# SOC_EMMC_SDMMC_PCIE_ADC.net
KiCad netlist of a schematic drawn in Altium Designer
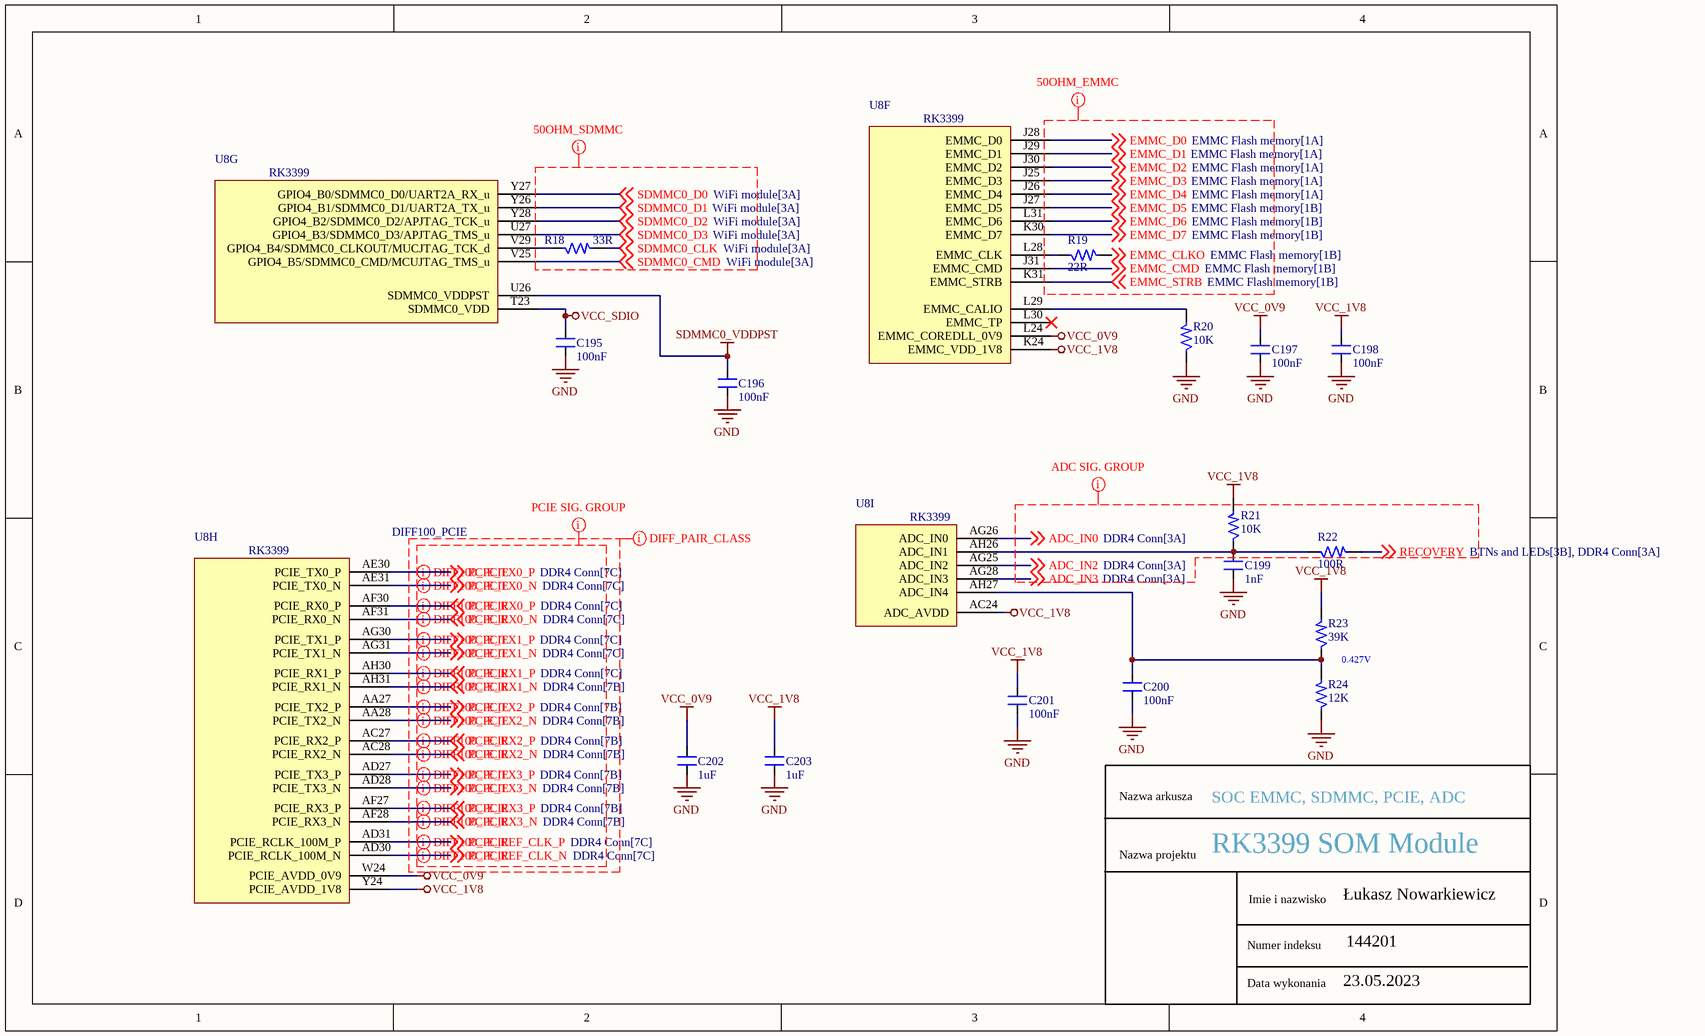
[diagram p0: SOC EMMC, SDMMC, PCIE, ADC.SchDoc]

(export (version "E")
  (design (tool "Eeschema 10.0.6"))
  (components
    (comp (ref "C195")
      (value "100nF")
      (footprint "CAP_0201")
      (description "0.1µF ±10% 25V Ceramic Capacitor X5R 0201 (0603 Metric)")
      (fields
        (field (name "MANUFACTURER") "TDK Corporation")
        (field (name "MANUFACTURER PART NUMBER") "C0603X5R1E104K030BB")
      )
      (libsource (lib "RK3399 _Module_Intlib") (part "CAP_100nF-25V-10%-0201"))
    )
    (comp (ref "C196")
      (value "100nF")
      (footprint "CAP_0201")
      (description "0.1µF ±10% 25V Ceramic Capacitor X5R 0201 (0603 Metric)")
      (fields
        (field (name "MANUFACTURER") "TDK Corporation")
        (field (name "MANUFACTURER PART NUMBER") "C0603X5R1E104K030BB")
      )
      (libsource (lib "RK3399 _Module_Intlib") (part "CAP_100nF-25V-10%-0201"))
    )
    (comp (ref "C197")
      (value "100nF")
      (footprint "CAP_0201")
      (description "0.1µF ±10% 25V Ceramic Capacitor X5R 0201 (0603 Metric)")
      (fields
        (field (name "MANUFACTURER") "TDK Corporation")
        (field (name "MANUFACTURER PART NUMBER") "C0603X5R1E104K030BB")
      )
      (libsource (lib "RK3399 _Module_Intlib") (part "CAP_100nF-25V-10%-0201"))
    )
    (comp (ref "C198")
      (value "100nF")
      (footprint "CAP_0201")
      (description "0.1µF ±10% 25V Ceramic Capacitor X5R 0201 (0603 Metric)")
      (fields
        (field (name "MANUFACTURER") "TDK Corporation")
        (field (name "MANUFACTURER PART NUMBER") "C0603X5R1E104K030BB")
      )
      (libsource (lib "RK3399 _Module_Intlib") (part "CAP_100nF-25V-10%-0201"))
    )
    (comp (ref "C199")
      (value "1nF")
      (footprint "CAP_0201")
      (description "1000pF ±10% 16V Ceramic Capacitor X7R 0201 (0603 Metric)")
      (fields
        (field (name "MANUFACTURER") "Murata Electronics")
        (field (name "MANUFACTURER PART NUMBER") "GRM033R71C102KA01D")
      )
      (libsource (lib "RK3399 _Module_Intlib") (part "CAP_1nF-16V-10%-0201"))
    )
    (comp (ref "C200")
      (value "100nF")
      (footprint "CAP_0201")
      (description "0.1µF ±10% 25V Ceramic Capacitor X5R 0201 (0603 Metric)")
      (fields
        (field (name "MANUFACTURER") "TDK Corporation")
        (field (name "MANUFACTURER PART NUMBER") "C0603X5R1E104K030BB")
      )
      (libsource (lib "RK3399 _Module_Intlib") (part "CAP_100nF-25V-10%-0201"))
    )
    (comp (ref "C201")
      (value "100nF")
      (footprint "CAP_0201")
      (description "0.1µF ±10% 25V Ceramic Capacitor X5R 0201 (0603 Metric)")
      (fields
        (field (name "MANUFACTURER") "TDK Corporation")
        (field (name "MANUFACTURER PART NUMBER") "C0603X5R1E104K030BB")
      )
      (libsource (lib "RK3399 _Module_Intlib") (part "CAP_100nF-25V-10%-0201"))
    )
    (comp (ref "C202")
      (value "1uF")
      (footprint "CAP_0201")
      (description "1µF ±20% 16V Ceramic Capacitor X5R 0201 (0603 Metric)")
      (fields
        (field (name "MANUFACTURER") "Samsung Electro-Mechanics")
        (field (name "MANUFACTURER PART NUMBER") "CL03A105MO3NRNH")
      )
      (libsource (lib "RK3399 _Module_Intlib") (part "CAP_1uF-16V-10%-0201"))
    )
    (comp (ref "C203")
      (value "1uF")
      (footprint "CAP_0201")
      (description "1µF ±20% 16V Ceramic Capacitor X5R 0201 (0603 Metric)")
      (fields
        (field (name "MANUFACTURER") "Samsung Electro-Mechanics")
        (field (name "MANUFACTURER PART NUMBER") "CL03A105MO3NRNH")
      )
      (libsource (lib "RK3399 _Module_Intlib") (part "CAP_1uF-16V-10%-0201"))
    )
    (comp (ref "R18")
      (value "33R")
      (footprint "RES_0201")
      (description "33 Ohms ±1% 0.05W, 1/20W Chip Resistor 0201 (0603 Metric) Thick Film")
      (fields
        (field (name "MANUFACTURER") "Yageo")
        (field (name "MANUFACTURER PART NUMBER") "RC0201FR-0733RL")
      )
      (libsource (lib "RK3399 _Module_Intlib") (part "RES_33R-0.05W-1%-0201"))
    )
    (comp (ref "R19")
      (value "22R")
      (footprint "RES_0201")
      (description "22 Ohms ±1% 0.05W, 1/20W Chip Resistor 0201 (0603 Metric) Moisture Resistant Thick Film")
      (fields
        (field (name "MANUFACTURER") "Yageo")
        (field (name "MANUFACTURER PART NUMBER") "RC0201FR-0722RL")
      )
      (libsource (lib "EsteemPCB_SOM_Course_schlib") (part "RES_22R-0.05W-1%-0201"))
    )
    (comp (ref "R20")
      (value "10K")
      (footprint "RES_0201")
      (description "10 kOhms ±1% 0.05W, 1/20W Chip Resistor 0201 (0603 Metric) Thick Film")
      (fields
        (field (name "MANUFACTURER") "Stackpole Electronics Inc")
        (field (name "MANUFACTURER PART NUMBER") "RMCF0201FT10K0")
      )
      (libsource (lib "RK3399 _Module_Intlib") (part "RES_10K-0.05W-1%-0201"))
    )
    (comp (ref "R21")
      (value "10K")
      (footprint "RES_0201")
      (description "10 kOhms ±1% 0.05W, 1/20W Chip Resistor 0201 (0603 Metric) Thick Film")
      (fields
        (field (name "MANUFACTURER") "Stackpole Electronics Inc")
        (field (name "MANUFACTURER PART NUMBER") "RMCF0201FT10K0")
      )
      (libsource (lib "RK3399 _Module_Intlib") (part "RES_10K-0.05W-1%-0201"))
    )
    (comp (ref "R22")
      (value "100R")
      (footprint "RES_0201")
      (description "100 kOhms ±1% 0.05W, 1/20W Chip Resistor 0201 (0603 Metric) Automotive AEC-Q200 Thick Film")
      (fields
        (field (name "MANUFACTURER") "Panasonic Electronic Components")
        (field (name "MANUFACTURER PART NUMBER") "ERJ-1GNF1003C")
      )
      (libsource (lib "RK3399 _Module_Intlib") (part "RES_100R-0.05W-1%-0201"))
    )
    (comp (ref "R23")
      (value "39K")
      (footprint "RES_0201")
      (description "39 kOhms ±1% 0.05W, 1/20W Chip Resistor 0201 (0603 Metric) Thick Film")
      (fields
        (field (name "MANUFACTURER") "Yageo")
        (field (name "MANUFACTURER PART NUMBER") "RC0201FR-0739KL")
      )
      (libsource (lib "RK3399 _Module_Intlib") (part "RES_39K-0.05W-1%-0201"))
    )
    (comp (ref "R24")
      (value "12K")
      (footprint "RES_0201")
      (description "12 kOhms ±1% 0.05W, 1/20W Chip Resistor 0201 (0603 Metric) Thick Film")
      (fields
        (field (name "MANUFACTURER") "Yageo")
        (field (name "MANUFACTURER PART NUMBER") "RC0201FR-0712KL")
      )
      (libsource (lib "RK3399 _Module_Intlib") (part "RES_12K-0.05W-1%-0201"))
    )
    (comp (ref "U8")
      (value "RK3399")
      (footprint "FBGA828_23_826X826")
      (description "RK3399 is a low power, high performance processor for computing, personal mobile.")
      (fields (field (name "MANUFACTURER") "Rockchip"))
      (libsource (lib "EsteemPCB_SOM_Course_intlib") (part "IC_RK3399-FCBGA828"))
    )
  )
  (nets
    (net (code "1") (name "ADC_IN0") (class "Default")
      (node (ref "U8") (pin "AG26") (pinfunction "ADC_IN0_AG26") (pintype "passive"))
    )
    (net (code "2") (name "ADC_IN2") (class "Default")
      (node (ref "U8") (pin "AG25") (pinfunction "ADC_IN2_AG25") (pintype "passive"))
    )
    (net (code "3") (name "ADC_IN3") (class "Default")
      (node (ref "U8") (pin "AG28") (pinfunction "ADC_IN3_AG28") (pintype "passive"))
    )
    (net (code "4") (name "EMMC_CLKO") (class "Default")
      (node (ref "R19") (pin "2") (pinfunction "2_2") (pintype "passive"))
    )
    (net (code "5") (name "EMMC_CMD") (class "Default")
      (node (ref "U8") (pin "J31") (pinfunction "EMMC_CMD_J31") (pintype "passive"))
    )
    (net (code "6") (name "EMMC_D0") (class "Default")
      (node (ref "U8") (pin "J28") (pinfunction "EMMC_D0_J28") (pintype "passive"))
    )
    (net (code "7") (name "EMMC_D1") (class "Default")
      (node (ref "U8") (pin "J29") (pinfunction "EMMC_D1_J29") (pintype "passive"))
    )
    (net (code "8") (name "EMMC_D2") (class "Default")
      (node (ref "U8") (pin "J30") (pinfunction "EMMC_D2_J30") (pintype "passive"))
    )
    (net (code "9") (name "EMMC_D3") (class "Default")
      (node (ref "U8") (pin "J25") (pinfunction "EMMC_D3_J25") (pintype "passive"))
    )
    (net (code "10") (name "EMMC_D4") (class "Default")
      (node (ref "U8") (pin "J26") (pinfunction "EMMC_D4_J26") (pintype "passive"))
    )
    (net (code "11") (name "EMMC_D5") (class "Default")
      (node (ref "U8") (pin "J27") (pinfunction "EMMC_D5_J27") (pintype "passive"))
    )
    (net (code "12") (name "EMMC_D6") (class "Default")
      (node (ref "U8") (pin "L31") (pinfunction "EMMC_D6_L31") (pintype "passive"))
    )
    (net (code "13") (name "EMMC_D7") (class "Default")
      (node (ref "U8") (pin "K30") (pinfunction "EMMC_D7_K30") (pintype "passive"))
    )
    (net (code "14") (name "EMMC_STRB") (class "Default")
      (node (ref "U8") (pin "K31") (pinfunction "EMMC_STRB_K31") (pintype "passive"))
    )
    (net (code "15") (name "GND") (class "Default")
      (node (ref "C195") (pin "1") (pinfunction "1_1") (pintype "passive"))
      (node (ref "C196") (pin "1") (pinfunction "1_1") (pintype "passive"))
      (node (ref "C197") (pin "1") (pinfunction "1_1") (pintype "passive"))
      (node (ref "C198") (pin "1") (pinfunction "1_1") (pintype "passive"))
      (node (ref "C199") (pin "1") (pinfunction "1_1") (pintype "passive"))
      (node (ref "C200") (pin "1") (pinfunction "1_1") (pintype "passive"))
      (node (ref "C201") (pin "1") (pinfunction "1_1") (pintype "passive"))
      (node (ref "C202") (pin "1") (pinfunction "1_1") (pintype "passive"))
      (node (ref "C203") (pin "1") (pinfunction "1_1") (pintype "passive"))
      (node (ref "R20") (pin "1") (pinfunction "1_1") (pintype "passive"))
      (node (ref "R24") (pin "1") (pinfunction "1_1") (pintype "passive"))
    )
    (net (code "16") (name "Net-(U8F-EMMC_CALIO)") (class "Default")
      (node (ref "R20") (pin "2") (pinfunction "2_2") (pintype "passive"))
      (node (ref "U8") (pin "L29") (pinfunction "EMMC_CALIO_L29") (pintype "passive"))
    )
    (net (code "17") (name "Net-(U8F-EMMC_CLK)") (class "Default")
      (node (ref "R19") (pin "1") (pinfunction "1_1") (pintype "passive"))
      (node (ref "U8") (pin "L28") (pinfunction "EMMC_CLK_L28") (pintype "passive"))
    )
    (net (code "18") (name "Net-(U8G-GPIO4_B4{slash}SDMMC0_CLKOUT{slash}MUCJTAG_TCK_d)") (class "Default")
      (node (ref "R18") (pin "1") (pinfunction "1_1") (pintype "passive"))
      (node (ref "U8") (pin "V29") (pinfunction "GPIO4_B4/SDMMC0_CLKOUT/MUCJTAG_TCK_d_V29") (pintype "passive"))
    )
    (net (code "19") (name "Net-(U8I-ADC_IN1)") (class "Default")
      (node (ref "C199") (pin "2") (pinfunction "2_2") (pintype "passive"))
      (node (ref "R21") (pin "1") (pinfunction "1_1") (pintype "passive"))
      (node (ref "R22") (pin "1") (pinfunction "1_1") (pintype "passive"))
      (node (ref "U8") (pin "AH26") (pinfunction "ADC_IN1_AH26") (pintype "passive"))
    )
    (net (code "20") (name "Net-(U8I-ADC_IN4)") (class "Default")
      (node (ref "C200") (pin "2") (pinfunction "2_2") (pintype "passive"))
      (node (ref "R23") (pin "1") (pinfunction "1_1") (pintype "passive"))
      (node (ref "R24") (pin "2") (pinfunction "2_2") (pintype "passive"))
      (node (ref "U8") (pin "AH27") (pinfunction "ADC_IN4_AH27") (pintype "passive"))
    )
    (net (code "21") (name "PCIE_REF_CLK_N") (class "Default")
      (node (ref "U8") (pin "AD30") (pinfunction "PCIE_RCLK_100M_N_AD30") (pintype "passive"))
    )
    (net (code "22") (name "PCIE_REF_CLK_P") (class "Default")
      (node (ref "U8") (pin "AD31") (pinfunction "PCIE_RCLK_100M_P_AD31") (pintype "passive"))
    )
    (net (code "23") (name "PCIE_RX0_N") (class "Default")
      (node (ref "U8") (pin "AF31") (pinfunction "PCIE_RX0_N_AF31") (pintype "passive"))
    )
    (net (code "24") (name "PCIE_RX0_P") (class "Default")
      (node (ref "U8") (pin "AF30") (pinfunction "PCIE_RX0_P_AF30") (pintype "passive"))
    )
    (net (code "25") (name "PCIE_RX1_N") (class "Default")
      (node (ref "U8") (pin "AH31") (pinfunction "PCIE_RX1_N_AH31") (pintype "passive"))
    )
    (net (code "26") (name "PCIE_RX1_P") (class "Default")
      (node (ref "U8") (pin "AH30") (pinfunction "PCIE_RX1_P_AH30") (pintype "passive"))
    )
    (net (code "27") (name "PCIE_RX2_N") (class "Default")
      (node (ref "U8") (pin "AC28") (pinfunction "PCIE_RX2_N_AC28") (pintype "passive"))
    )
    (net (code "28") (name "PCIE_RX2_P") (class "Default")
      (node (ref "U8") (pin "AC27") (pinfunction "PCIE_RX2_P_AC27") (pintype "passive"))
    )
    (net (code "29") (name "PCIE_RX3_N") (class "Default")
      (node (ref "U8") (pin "AF28") (pinfunction "PCIE_RX3_N_AF28") (pintype "passive"))
    )
    (net (code "30") (name "PCIE_RX3_P") (class "Default")
      (node (ref "U8") (pin "AF27") (pinfunction "PCIE_RX3_P_AF27") (pintype "passive"))
    )
    (net (code "31") (name "PCIE_TX0_N") (class "Default")
      (node (ref "U8") (pin "AE31") (pinfunction "PCIE_TX0_N_AE31") (pintype "passive"))
    )
    (net (code "32") (name "PCIE_TX0_P") (class "Default")
      (node (ref "U8") (pin "AE30") (pinfunction "PCIE_TX0_P_AE30") (pintype "passive"))
    )
    (net (code "33") (name "PCIE_TX1_N") (class "Default")
      (node (ref "U8") (pin "AG31") (pinfunction "PCIE_TX1_N_AG31") (pintype "passive"))
    )
    (net (code "34") (name "PCIE_TX1_P") (class "Default")
      (node (ref "U8") (pin "AG30") (pinfunction "PCIE_TX1_P_AG30") (pintype "passive"))
    )
    (net (code "35") (name "PCIE_TX2_N") (class "Default")
      (node (ref "U8") (pin "AA28") (pinfunction "PCIE_TX2_N_AA28") (pintype "passive"))
    )
    (net (code "36") (name "PCIE_TX2_P") (class "Default")
      (node (ref "U8") (pin "AA27") (pinfunction "PCIE_TX2_P_AA27") (pintype "passive"))
    )
    (net (code "37") (name "PCIE_TX3_N") (class "Default")
      (node (ref "U8") (pin "AD28") (pinfunction "PCIE_TX3_N_AD28") (pintype "passive"))
    )
    (net (code "38") (name "PCIE_TX3_P") (class "Default")
      (node (ref "U8") (pin "AD27") (pinfunction "PCIE_TX3_P_AD27") (pintype "passive"))
    )
    (net (code "39") (name "RECOVERY") (class "Default")
      (node (ref "R22") (pin "2") (pinfunction "2_2") (pintype "passive"))
    )
    (net (code "40") (name "SDMMC0_CLK") (class "Default")
      (node (ref "R18") (pin "2") (pinfunction "2_2") (pintype "passive"))
    )
    (net (code "41") (name "SDMMC0_CMD") (class "Default")
      (node (ref "U8") (pin "V25") (pinfunction "GPIO4_B5/SDMMC0_CMD/MCUJTAG_TMS_u_V25") (pintype "passive"))
    )
    (net (code "42") (name "SDMMC0_D0") (class "Default")
      (node (ref "U8") (pin "Y27") (pinfunction "GPIO4_B0/SDMMC0_D0/UART2A_RX_u_Y27") (pintype "passive"))
    )
    (net (code "43") (name "SDMMC0_D1") (class "Default")
      (node (ref "U8") (pin "Y26") (pinfunction "GPIO4_B1/SDMMC0_D1/UART2A_TX_u_Y26") (pintype "passive"))
    )
    (net (code "44") (name "SDMMC0_D2") (class "Default")
      (node (ref "U8") (pin "Y28") (pinfunction "GPIO4_B2/SDMMC0_D2/APJTAG_TCK_u_Y28") (pintype "passive"))
    )
    (net (code "45") (name "SDMMC0_D3") (class "Default")
      (node (ref "U8") (pin "U27") (pinfunction "GPIO4_B3/SDMMC0_D3/APJTAG_TMS_u_U27") (pintype "passive"))
    )
    (net (code "46") (name "SDMMC0_VDDPST") (class "Default")
      (node (ref "C196") (pin "2") (pinfunction "2_2") (pintype "passive"))
      (node (ref "U8") (pin "U26") (pinfunction "SDMMC0_VDDPST_U26") (pintype "passive"))
    )
    (net (code "47") (name "VCC_0V9") (class "Default")
      (node (ref "C197") (pin "2") (pinfunction "2_2") (pintype "passive"))
      (node (ref "C202") (pin "2") (pinfunction "2_2") (pintype "passive"))
      (node (ref "U8") (pin "L24") (pinfunction "EMMC_COREDLL_0V9_L24") (pintype "passive"))
      (node (ref "U8") (pin "W24") (pinfunction "PCIE_AVDD_0V9_W24") (pintype "passive"))
    )
    (net (code "48") (name "VCC_1V8") (class "Default")
      (node (ref "C198") (pin "2") (pinfunction "2_2") (pintype "passive"))
      (node (ref "C201") (pin "2") (pinfunction "2_2") (pintype "passive"))
      (node (ref "C203") (pin "2") (pinfunction "2_2") (pintype "passive"))
      (node (ref "R21") (pin "2") (pinfunction "2_2") (pintype "passive"))
      (node (ref "R23") (pin "2") (pinfunction "2_2") (pintype "passive"))
      (node (ref "U8") (pin "AC24") (pinfunction "ADC_AVDD_AC24") (pintype "passive"))
      (node (ref "U8") (pin "K24") (pinfunction "EMMC_VDD_1V8_K24") (pintype "passive"))
      (node (ref "U8") (pin "Y24") (pinfunction "PCIE_AVDD_1V8_Y24") (pintype "passive"))
    )
    (net (code "49") (name "VCC_SDIO") (class "Default")
      (node (ref "C195") (pin "2") (pinfunction "2_2") (pintype "passive"))
      (node (ref "U8") (pin "T23") (pinfunction "SDMMC0_VDD_T23") (pintype "passive"))
    )
    (net (code "50") (name "unconnected-(U8F-EMMC_TP-PadL30)") (class "Default")
      (node (ref "U8") (pin "L30") (pinfunction "EMMC_TP_L30") (pintype "passive+no_connect"))
    )
  )
)
